# USB_circuit.net
KiCad netlist of a schematic drawn in EAGLE
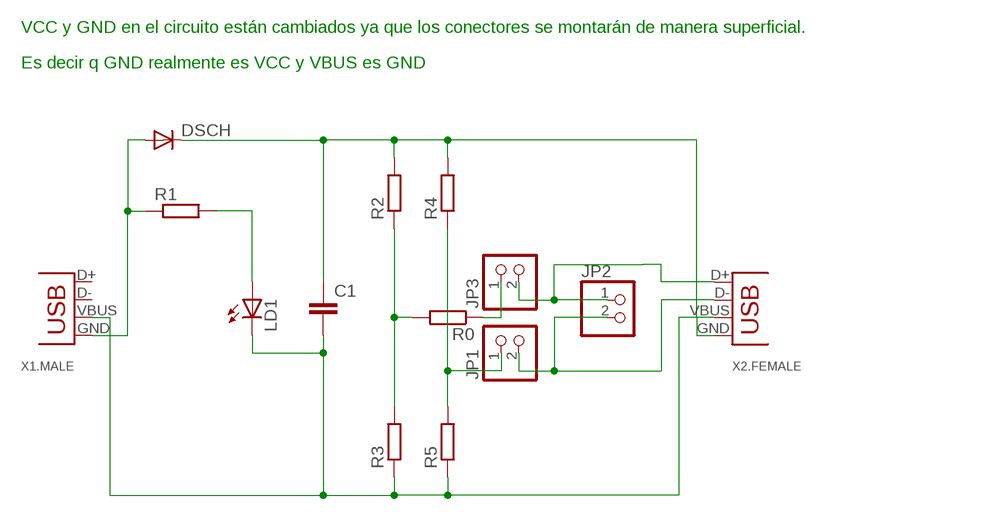
[diagram p0: schematic, sheet 1]

(export (version "E")
  (design (tool "Eeschema 10.0.6"))
  (components
    (comp (ref "C1")
      (value "C-EUC1812")
      (footprint "eagle-import:C1812")
      (libsource (lib "eagle-import") (part "C-EUC1812"))
    )
    (comp (ref "DSCH")
      (value "DIODE-SOD123")
      (footprint "eagle-import:SOD123")
      (libsource (lib "eagle-import") (part "DIODE-SOD123"))
    )
    (comp (ref "JP1")
      (value "PINHD-1X2_2.54")
      (footprint "eagle-import:1X02")
      (libsource (lib "eagle-import") (part "PINHD-1X2_2.54"))
    )
    (comp (ref "JP2")
      (value "PINHD-1X2_2.54")
      (footprint "eagle-import:1X02")
      (libsource (lib "eagle-import") (part "PINHD-1X2_2.54"))
    )
    (comp (ref "JP3")
      (value "PINHD-1X2_2.54")
      (footprint "eagle-import:1X02")
      (libsource (lib "eagle-import") (part "PINHD-1X2_2.54"))
    )
    (comp (ref "LD1")
      (value "LEDCHIPLED_1206")
      (footprint "eagle-import:CHIPLED_1206")
      (libsource (lib "eagle-import") (part "LEDCHIPLED_1206"))
    )
    (comp (ref "R0")
      (value "R-EU_R1206")
      (footprint "eagle-import:R1206")
      (libsource (lib "eagle-import") (part "R-EU_R1206"))
    )
    (comp (ref "R1")
      (value "R-EU_R1206")
      (footprint "eagle-import:R1206")
      (libsource (lib "eagle-import") (part "R-EU_R1206"))
    )
    (comp (ref "R2")
      (value "R-EU_R1206")
      (footprint "eagle-import:R1206")
      (libsource (lib "eagle-import") (part "R-EU_R1206"))
    )
    (comp (ref "R3")
      (value "R-EU_R1206")
      (footprint "eagle-import:R1206")
      (libsource (lib "eagle-import") (part "R-EU_R1206"))
    )
    (comp (ref "R4")
      (value "R-EU_R1206")
      (footprint "eagle-import:R1206")
      (libsource (lib "eagle-import") (part "R-EU_R1206"))
    )
    (comp (ref "R5")
      (value "R-EU_R1206")
      (footprint "eagle-import:R1206")
      (libsource (lib "eagle-import") (part "R-EU_R1206"))
    )
    (comp (ref "X1.MALE")
      (value "USB-A-H")
      (footprint "eagle-import:USB-A-H")
      (libsource (lib "eagle-import") (part "USB-A-H"))
    )
    (comp (ref "X2.FEMALE")
      (value "USB-A-H")
      (footprint "eagle-import:USB-A-H")
      (libsource (lib "eagle-import") (part "USB-A-H"))
    )
  )
  (nets
    (net (code "1") (name "Net-(C1-Pad1)") (class "Default")
      (node (ref "C1") (pin "1") (pinfunction "1_1") (pintype "passive"))
      (node (ref "DSCH") (pin "C") (pinfunction "C_C") (pintype "passive"))
      (node (ref "R2") (pin "2") (pinfunction "2_2") (pintype "passive"))
      (node (ref "R4") (pin "2") (pinfunction "2_2") (pintype "passive"))
      (node (ref "X2.FEMALE") (pin "GND") (pinfunction "GND_GND") (pintype "bidirectional"))
    )
    (net (code "2") (name "Net-(C1-Pad2)") (class "Default")
      (node (ref "C1") (pin "2") (pinfunction "2_2") (pintype "passive"))
      (node (ref "LD1") (pin "C") (pinfunction "C_C") (pintype "passive"))
      (node (ref "R3") (pin "1") (pinfunction "1_1") (pintype "passive"))
      (node (ref "R5") (pin "1") (pinfunction "1_1") (pintype "passive"))
      (node (ref "X1.MALE") (pin "VBUS") (pinfunction "VBUS_VBUS") (pintype "bidirectional"))
      (node (ref "X2.FEMALE") (pin "VBUS") (pinfunction "VBUS_VBUS") (pintype "bidirectional"))
    )
    (net (code "3") (name "Net-(DSCH-PadA)") (class "Default")
      (node (ref "DSCH") (pin "A") (pinfunction "A_A") (pintype "passive"))
      (node (ref "R1") (pin "1") (pinfunction "1_1") (pintype "passive"))
      (node (ref "X1.MALE") (pin "GND") (pinfunction "GND_GND") (pintype "bidirectional"))
    )
    (net (code "4") (name "Net-(JP1-Pad1)") (class "Default")
      (node (ref "JP1") (pin "1") (pinfunction "1_1") (pintype "passive"))
      (node (ref "R4") (pin "1") (pinfunction "1_1") (pintype "passive"))
      (node (ref "R5") (pin "2") (pinfunction "2_2") (pintype "passive"))
    )
    (net (code "5") (name "Net-(JP1-Pad2)") (class "Default")
      (node (ref "JP1") (pin "2") (pinfunction "2_2") (pintype "passive"))
      (node (ref "JP2") (pin "2") (pinfunction "2_2") (pintype "passive"))
      (node (ref "X2.FEMALE") (pin "D-") (pinfunction "D-_D-") (pintype "bidirectional"))
    )
    (net (code "6") (name "Net-(JP2-Pad1)") (class "Default")
      (node (ref "JP2") (pin "1") (pinfunction "1_1") (pintype "passive"))
      (node (ref "JP3") (pin "2") (pinfunction "2_2") (pintype "passive"))
      (node (ref "X2.FEMALE") (pin "D+") (pinfunction "D+_D+") (pintype "bidirectional"))
    )
    (net (code "7") (name "Net-(JP3-Pad1)") (class "Default")
      (node (ref "JP3") (pin "1") (pinfunction "1_1") (pintype "passive"))
      (node (ref "R0") (pin "1") (pinfunction "1_1") (pintype "passive"))
    )
    (net (code "8") (name "Net-(LD1-PadA)") (class "Default")
      (node (ref "LD1") (pin "A") (pinfunction "A_A") (pintype "passive"))
      (node (ref "R1") (pin "2") (pinfunction "2_2") (pintype "passive"))
    )
    (net (code "9") (name "Net-(R0-Pad2)") (class "Default")
      (node (ref "R0") (pin "2") (pinfunction "2_2") (pintype "passive"))
      (node (ref "R2") (pin "1") (pinfunction "1_1") (pintype "passive"))
      (node (ref "R3") (pin "2") (pinfunction "2_2") (pintype "passive"))
    )
    (net (code "10") (name "unconnected-(X1.MALE-PadD+)") (class "Default")
      (node (ref "X1.MALE") (pin "D+") (pinfunction "D+_D+") (pintype "bidirectional"))
    )
    (net (code "11") (name "unconnected-(X1.MALE-PadD-)") (class "Default")
      (node (ref "X1.MALE") (pin "D-") (pinfunction "D-_D-") (pintype "bidirectional"))
    )
  )
)
